# CNY.net
KiCad netlist of a schematic drawn in EAGLE
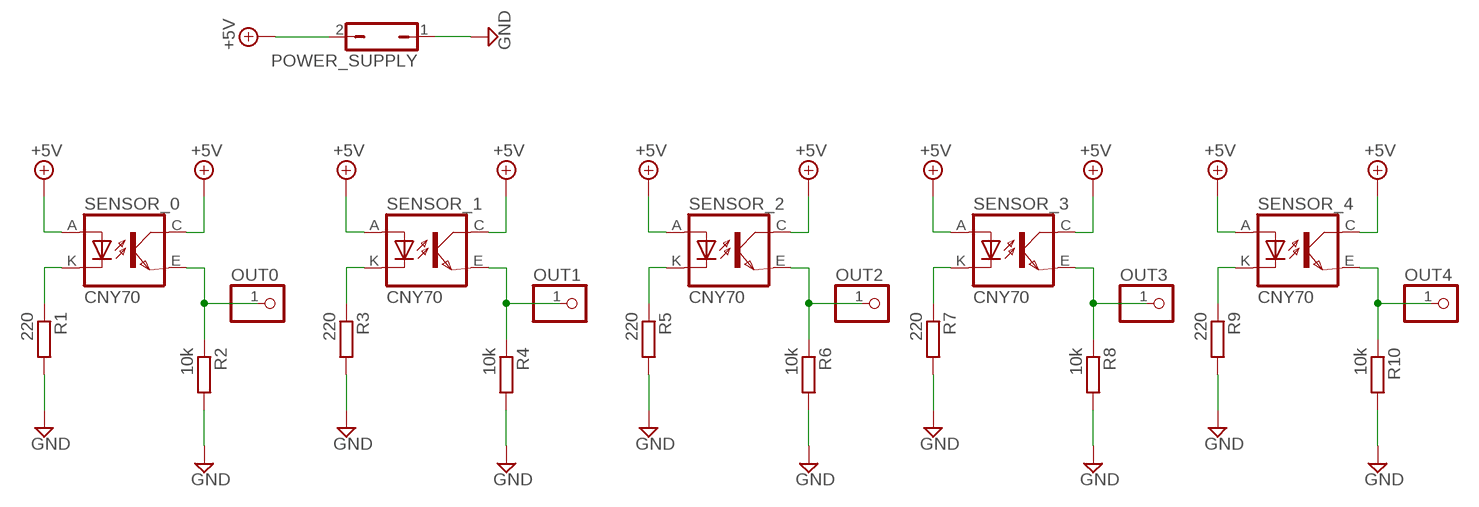
[diagram p0: schematic, sheet 1]

(export (version "E")
  (design (tool "Eeschema 10.0.6"))
  (components
    (comp (ref "OUT0")
      (value "PINHD-1X1")
      (footprint "eagle-import:1X01")
      (libsource (lib "eagle-import") (part "PINHD-1X1"))
    )
    (comp (ref "OUT1")
      (value "PINHD-1X1")
      (footprint "eagle-import:1X01")
      (libsource (lib "eagle-import") (part "PINHD-1X1"))
    )
    (comp (ref "OUT2")
      (value "PINHD-1X1")
      (footprint "eagle-import:1X01")
      (libsource (lib "eagle-import") (part "PINHD-1X1"))
    )
    (comp (ref "OUT3")
      (value "PINHD-1X1")
      (footprint "eagle-import:1X01")
      (libsource (lib "eagle-import") (part "PINHD-1X1"))
    )
    (comp (ref "OUT4")
      (value "PINHD-1X1")
      (footprint "eagle-import:1X01")
      (libsource (lib "eagle-import") (part "PINHD-1X1"))
    )
    (comp (ref "POWER_SUPPLY")
      (value "JP1Q")
      (footprint "eagle-import:JP1")
      (libsource (lib "eagle-import") (part "JP1Q"))
    )
    (comp (ref "R1")
      (value "220")
      (footprint "eagle-import:0204_5")
      (libsource (lib "eagle-import") (part "R-EU_0204/5"))
    )
    (comp (ref "R2")
      (value "10k")
      (footprint "eagle-import:0204_5")
      (libsource (lib "eagle-import") (part "R-EU_0204/5"))
    )
    (comp (ref "R3")
      (value "220")
      (footprint "eagle-import:0204_5")
      (libsource (lib "eagle-import") (part "R-EU_0204/5"))
    )
    (comp (ref "R4")
      (value "10k")
      (footprint "eagle-import:0204_5")
      (libsource (lib "eagle-import") (part "R-EU_0204/5"))
    )
    (comp (ref "R5")
      (value "220")
      (footprint "eagle-import:0204_5")
      (libsource (lib "eagle-import") (part "R-EU_0204/5"))
    )
    (comp (ref "R6")
      (value "10k")
      (footprint "eagle-import:0204_5")
      (libsource (lib "eagle-import") (part "R-EU_0204/5"))
    )
    (comp (ref "R7")
      (value "220")
      (footprint "eagle-import:0204_5")
      (libsource (lib "eagle-import") (part "R-EU_0204/5"))
    )
    (comp (ref "R8")
      (value "10k")
      (footprint "eagle-import:0204_5")
      (libsource (lib "eagle-import") (part "R-EU_0204/5"))
    )
    (comp (ref "R9")
      (value "220")
      (footprint "eagle-import:0204_5")
      (libsource (lib "eagle-import") (part "R-EU_0204/5"))
    )
    (comp (ref "R10")
      (value "10k")
      (footprint "eagle-import:0204_5")
      (libsource (lib "eagle-import") (part "R-EU_0204/5"))
    )
    (comp (ref "SENSOR_0")
      (value "CNY70")
      (footprint "eagle-import:4")
      (libsource (lib "eagle-import") (part "CNY70"))
    )
    (comp (ref "SENSOR_1")
      (value "CNY70")
      (footprint "eagle-import:4")
      (libsource (lib "eagle-import") (part "CNY70"))
    )
    (comp (ref "SENSOR_2")
      (value "CNY70")
      (footprint "eagle-import:4")
      (libsource (lib "eagle-import") (part "CNY70"))
    )
    (comp (ref "SENSOR_3")
      (value "CNY70")
      (footprint "eagle-import:4")
      (libsource (lib "eagle-import") (part "CNY70"))
    )
    (comp (ref "SENSOR_4")
      (value "CNY70")
      (footprint "eagle-import:4")
      (libsource (lib "eagle-import") (part "CNY70"))
    )
  )
  (nets
    (net (code "1") (name "+5V") (class "Default")
      (node (ref "POWER_SUPPLY") (pin "2") (pinfunction "2_2") (pintype "passive"))
      (node (ref "SENSOR_0") (pin "A") (pinfunction "A_A") (pintype "passive"))
      (node (ref "SENSOR_0") (pin "C") (pinfunction "COL_C") (pintype "passive"))
      (node (ref "SENSOR_1") (pin "A") (pinfunction "A_A") (pintype "passive"))
      (node (ref "SENSOR_1") (pin "C") (pinfunction "COL_C") (pintype "passive"))
      (node (ref "SENSOR_2") (pin "A") (pinfunction "A_A") (pintype "passive"))
      (node (ref "SENSOR_2") (pin "C") (pinfunction "COL_C") (pintype "passive"))
      (node (ref "SENSOR_3") (pin "A") (pinfunction "A_A") (pintype "passive"))
      (node (ref "SENSOR_3") (pin "C") (pinfunction "COL_C") (pintype "passive"))
      (node (ref "SENSOR_4") (pin "A") (pinfunction "A_A") (pintype "passive"))
      (node (ref "SENSOR_4") (pin "C") (pinfunction "COL_C") (pintype "passive"))
    )
    (net (code "2") (name "GND") (class "Default")
      (node (ref "POWER_SUPPLY") (pin "1") (pinfunction "1_1") (pintype "passive"))
      (node (ref "R1") (pin "2") (pinfunction "2_2") (pintype "passive"))
      (node (ref "R10") (pin "2") (pinfunction "2_2") (pintype "passive"))
      (node (ref "R2") (pin "2") (pinfunction "2_2") (pintype "passive"))
      (node (ref "R3") (pin "2") (pinfunction "2_2") (pintype "passive"))
      (node (ref "R4") (pin "2") (pinfunction "2_2") (pintype "passive"))
      (node (ref "R5") (pin "2") (pinfunction "2_2") (pintype "passive"))
      (node (ref "R6") (pin "2") (pinfunction "2_2") (pintype "passive"))
      (node (ref "R7") (pin "2") (pinfunction "2_2") (pintype "passive"))
      (node (ref "R8") (pin "2") (pinfunction "2_2") (pintype "passive"))
      (node (ref "R9") (pin "2") (pinfunction "2_2") (pintype "passive"))
    )
    (net (code "3") (name "Net-(SENSOR_0-C)") (class "Default")
      (node (ref "R1") (pin "1") (pinfunction "1_1") (pintype "passive"))
      (node (ref "SENSOR_0") (pin "K") (pinfunction "C_K") (pintype "passive"))
    )
    (net (code "4") (name "Net-(SENSOR_0-EMI)") (class "Default")
      (node (ref "OUT0") (pin "1") (pinfunction "1_1") (pintype "passive"))
      (node (ref "R2") (pin "1") (pinfunction "1_1") (pintype "passive"))
      (node (ref "SENSOR_0") (pin "E") (pinfunction "EMI_E") (pintype "passive"))
    )
    (net (code "5") (name "Net-(SENSOR_1-C)") (class "Default")
      (node (ref "R3") (pin "1") (pinfunction "1_1") (pintype "passive"))
      (node (ref "SENSOR_1") (pin "K") (pinfunction "C_K") (pintype "passive"))
    )
    (net (code "6") (name "Net-(SENSOR_1-EMI)") (class "Default")
      (node (ref "OUT1") (pin "1") (pinfunction "1_1") (pintype "passive"))
      (node (ref "R4") (pin "1") (pinfunction "1_1") (pintype "passive"))
      (node (ref "SENSOR_1") (pin "E") (pinfunction "EMI_E") (pintype "passive"))
    )
    (net (code "7") (name "Net-(SENSOR_2-C)") (class "Default")
      (node (ref "R5") (pin "1") (pinfunction "1_1") (pintype "passive"))
      (node (ref "SENSOR_2") (pin "K") (pinfunction "C_K") (pintype "passive"))
    )
    (net (code "8") (name "Net-(SENSOR_2-EMI)") (class "Default")
      (node (ref "OUT2") (pin "1") (pinfunction "1_1") (pintype "passive"))
      (node (ref "R6") (pin "1") (pinfunction "1_1") (pintype "passive"))
      (node (ref "SENSOR_2") (pin "E") (pinfunction "EMI_E") (pintype "passive"))
    )
    (net (code "9") (name "Net-(SENSOR_3-C)") (class "Default")
      (node (ref "R7") (pin "1") (pinfunction "1_1") (pintype "passive"))
      (node (ref "SENSOR_3") (pin "K") (pinfunction "C_K") (pintype "passive"))
    )
    (net (code "10") (name "Net-(SENSOR_3-EMI)") (class "Default")
      (node (ref "OUT3") (pin "1") (pinfunction "1_1") (pintype "passive"))
      (node (ref "R8") (pin "1") (pinfunction "1_1") (pintype "passive"))
      (node (ref "SENSOR_3") (pin "E") (pinfunction "EMI_E") (pintype "passive"))
    )
    (net (code "11") (name "Net-(SENSOR_4-C)") (class "Default")
      (node (ref "R9") (pin "1") (pinfunction "1_1") (pintype "passive"))
      (node (ref "SENSOR_4") (pin "K") (pinfunction "C_K") (pintype "passive"))
    )
    (net (code "12") (name "Net-(SENSOR_4-EMI)") (class "Default")
      (node (ref "OUT4") (pin "1") (pinfunction "1_1") (pintype "passive"))
      (node (ref "R10") (pin "1") (pinfunction "1_1") (pintype "passive"))
      (node (ref "SENSOR_4") (pin "E") (pinfunction "EMI_E") (pintype "passive"))
    )
  )
)
